# Sheet1.net
KiCad netlist of a schematic drawn in Altium Designer
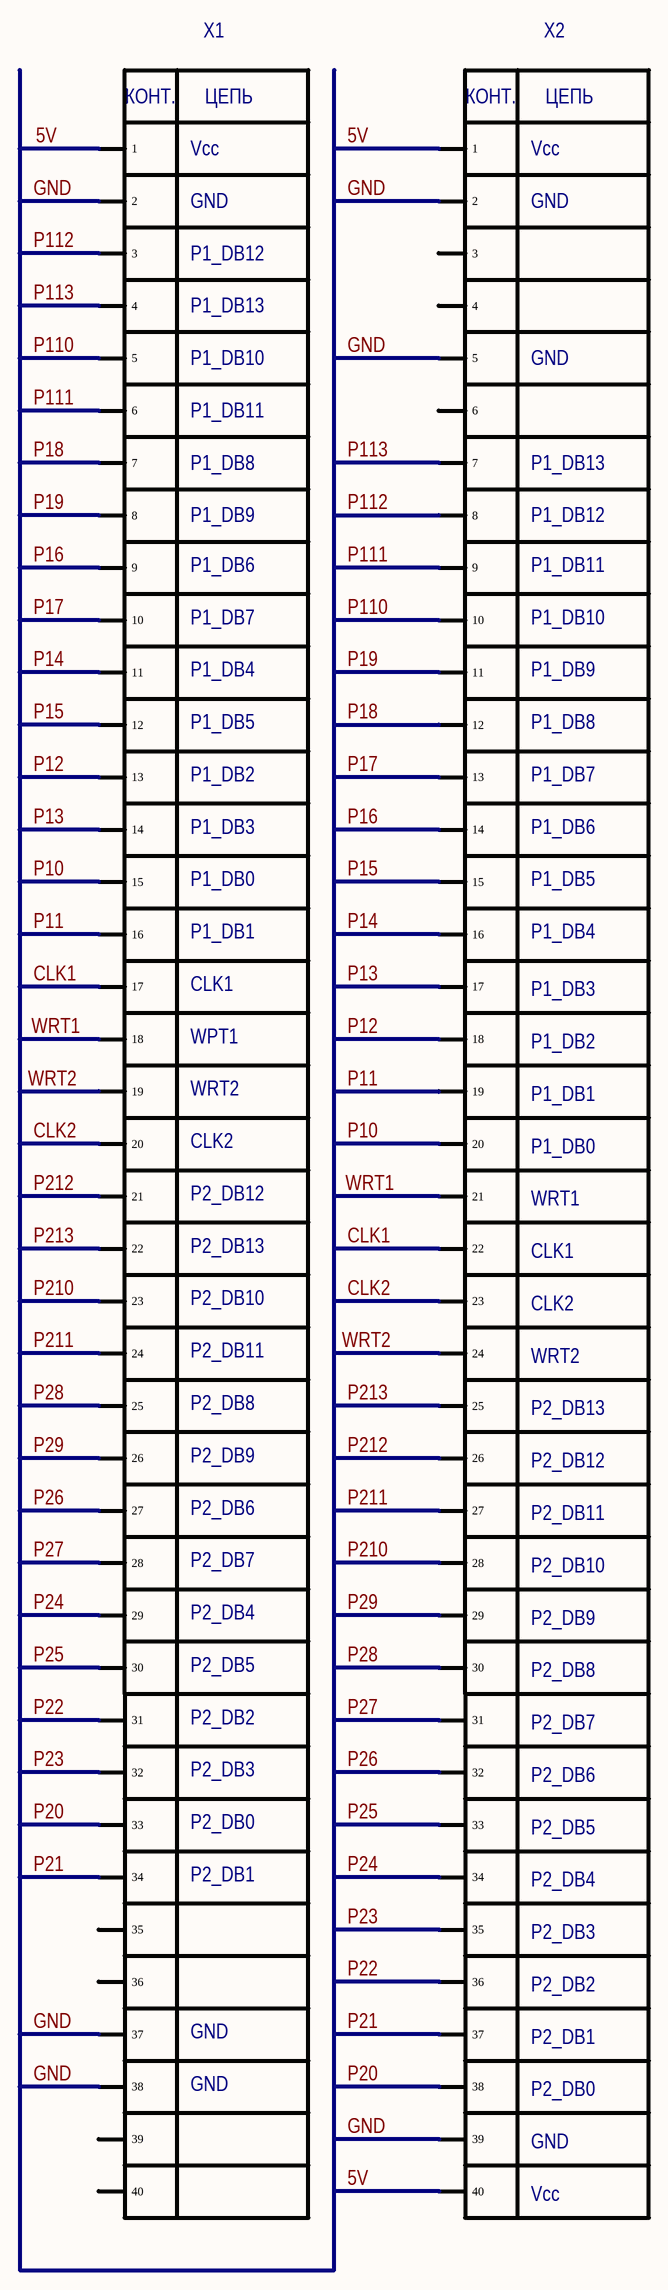
[diagram p0: Sheet1.SchDoc]

(export (version "E")
  (design (tool "Eeschema 10.0.6"))
  (components
    (comp (ref "X1")
      (value "PLD40")
      (footprint "PLD-40")
      (description "Штыри на плату, шаг 2.54мм., двухрядные")
      (libsource (lib "ConnectorsM") (part "PLD40"))
    )
    (comp (ref "X2")
      (value "PLD40")
      (footprint "PLD-40")
      (description "Штыри на плату, шаг 2.54мм., двухрядные")
      (libsource (lib "ConnectorsM") (part "PLD40"))
    )
  )
  (nets
    (net (code "1") (name "/5V") (class "Default")
      (node (ref "X1") (pin "1") (pinfunction "1_1") (pintype "passive"))
      (node (ref "X2") (pin "1") (pinfunction "1_1") (pintype "passive"))
      (node (ref "X2") (pin "40") (pinfunction "40_40") (pintype "passive"))
    )
    (net (code "2") (name "/CLK1") (class "Default")
      (node (ref "X1") (pin "17") (pinfunction "17_17") (pintype "passive"))
      (node (ref "X2") (pin "22") (pinfunction "22_22") (pintype "passive"))
    )
    (net (code "3") (name "/CLK2") (class "Default")
      (node (ref "X1") (pin "20") (pinfunction "20_20") (pintype "passive"))
      (node (ref "X2") (pin "23") (pinfunction "23_23") (pintype "passive"))
    )
    (net (code "4") (name "/GND") (class "Default")
      (node (ref "X1") (pin "2") (pinfunction "2_2") (pintype "passive"))
      (node (ref "X1") (pin "37") (pinfunction "37_37") (pintype "passive"))
      (node (ref "X1") (pin "38") (pinfunction "38_38") (pintype "passive"))
      (node (ref "X2") (pin "2") (pinfunction "2_2") (pintype "passive"))
      (node (ref "X2") (pin "39") (pinfunction "39_39") (pintype "passive"))
      (node (ref "X2") (pin "5") (pinfunction "5_5") (pintype "passive"))
    )
    (net (code "5") (name "/P10") (class "Default")
      (node (ref "X1") (pin "15") (pinfunction "15_15") (pintype "passive"))
      (node (ref "X2") (pin "20") (pinfunction "20_20") (pintype "passive"))
    )
    (net (code "6") (name "/P11") (class "Default")
      (node (ref "X1") (pin "16") (pinfunction "16_16") (pintype "passive"))
      (node (ref "X2") (pin "19") (pinfunction "19_19") (pintype "passive"))
    )
    (net (code "7") (name "/P12") (class "Default")
      (node (ref "X1") (pin "13") (pinfunction "13_13") (pintype "passive"))
      (node (ref "X2") (pin "18") (pinfunction "18_18") (pintype "passive"))
    )
    (net (code "8") (name "/P13") (class "Default")
      (node (ref "X1") (pin "14") (pinfunction "14_14") (pintype "passive"))
      (node (ref "X2") (pin "17") (pinfunction "17_17") (pintype "passive"))
    )
    (net (code "9") (name "/P14") (class "Default")
      (node (ref "X1") (pin "11") (pinfunction "11_11") (pintype "passive"))
      (node (ref "X2") (pin "16") (pinfunction "16_16") (pintype "passive"))
    )
    (net (code "10") (name "/P15") (class "Default")
      (node (ref "X1") (pin "12") (pinfunction "12_12") (pintype "passive"))
      (node (ref "X2") (pin "15") (pinfunction "15_15") (pintype "passive"))
    )
    (net (code "11") (name "/P16") (class "Default")
      (node (ref "X1") (pin "9") (pinfunction "9_9") (pintype "passive"))
      (node (ref "X2") (pin "14") (pinfunction "14_14") (pintype "passive"))
    )
    (net (code "12") (name "/P17") (class "Default")
      (node (ref "X1") (pin "10") (pinfunction "10_10") (pintype "passive"))
      (node (ref "X2") (pin "13") (pinfunction "13_13") (pintype "passive"))
    )
    (net (code "13") (name "/P18") (class "Default")
      (node (ref "X1") (pin "7") (pinfunction "7_7") (pintype "passive"))
      (node (ref "X2") (pin "12") (pinfunction "12_12") (pintype "passive"))
    )
    (net (code "14") (name "/P19") (class "Default")
      (node (ref "X1") (pin "8") (pinfunction "8_8") (pintype "passive"))
      (node (ref "X2") (pin "11") (pinfunction "11_11") (pintype "passive"))
    )
    (net (code "15") (name "/P20") (class "Default")
      (node (ref "X1") (pin "33") (pinfunction "33_33") (pintype "passive"))
      (node (ref "X2") (pin "38") (pinfunction "38_38") (pintype "passive"))
    )
    (net (code "16") (name "/P21") (class "Default")
      (node (ref "X1") (pin "34") (pinfunction "34_34") (pintype "passive"))
      (node (ref "X2") (pin "37") (pinfunction "37_37") (pintype "passive"))
    )
    (net (code "17") (name "/P22") (class "Default")
      (node (ref "X1") (pin "31") (pinfunction "31_31") (pintype "passive"))
      (node (ref "X2") (pin "36") (pinfunction "36_36") (pintype "passive"))
    )
    (net (code "18") (name "/P23") (class "Default")
      (node (ref "X1") (pin "32") (pinfunction "32_32") (pintype "passive"))
      (node (ref "X2") (pin "35") (pinfunction "35_35") (pintype "passive"))
    )
    (net (code "19") (name "/P24") (class "Default")
      (node (ref "X1") (pin "29") (pinfunction "29_29") (pintype "passive"))
      (node (ref "X2") (pin "34") (pinfunction "34_34") (pintype "passive"))
    )
    (net (code "20") (name "/P25") (class "Default")
      (node (ref "X1") (pin "30") (pinfunction "30_30") (pintype "passive"))
      (node (ref "X2") (pin "33") (pinfunction "33_33") (pintype "passive"))
    )
    (net (code "21") (name "/P26") (class "Default")
      (node (ref "X1") (pin "27") (pinfunction "27_27") (pintype "passive"))
      (node (ref "X2") (pin "32") (pinfunction "32_32") (pintype "passive"))
    )
    (net (code "22") (name "/P27") (class "Default")
      (node (ref "X1") (pin "28") (pinfunction "28_28") (pintype "passive"))
      (node (ref "X2") (pin "31") (pinfunction "31_31") (pintype "passive"))
    )
    (net (code "23") (name "/P28") (class "Default")
      (node (ref "X1") (pin "25") (pinfunction "25_25") (pintype "passive"))
      (node (ref "X2") (pin "30") (pinfunction "30_30") (pintype "passive"))
    )
    (net (code "24") (name "/P29") (class "Default")
      (node (ref "X1") (pin "26") (pinfunction "26_26") (pintype "passive"))
      (node (ref "X2") (pin "29") (pinfunction "29_29") (pintype "passive"))
    )
    (net (code "25") (name "/P110") (class "Default")
      (node (ref "X1") (pin "5") (pinfunction "5_5") (pintype "passive"))
      (node (ref "X2") (pin "10") (pinfunction "10_10") (pintype "passive"))
    )
    (net (code "26") (name "/P111") (class "Default")
      (node (ref "X1") (pin "6") (pinfunction "6_6") (pintype "passive"))
      (node (ref "X2") (pin "9") (pinfunction "9_9") (pintype "passive"))
    )
    (net (code "27") (name "/P112") (class "Default")
      (node (ref "X1") (pin "3") (pinfunction "3_3") (pintype "passive"))
      (node (ref "X2") (pin "8") (pinfunction "8_8") (pintype "passive"))
    )
    (net (code "28") (name "/P113") (class "Default")
      (node (ref "X1") (pin "4") (pinfunction "4_4") (pintype "passive"))
      (node (ref "X2") (pin "7") (pinfunction "7_7") (pintype "passive"))
    )
    (net (code "29") (name "/P210") (class "Default")
      (node (ref "X1") (pin "23") (pinfunction "23_23") (pintype "passive"))
      (node (ref "X2") (pin "28") (pinfunction "28_28") (pintype "passive"))
    )
    (net (code "30") (name "/P211") (class "Default")
      (node (ref "X1") (pin "24") (pinfunction "24_24") (pintype "passive"))
      (node (ref "X2") (pin "27") (pinfunction "27_27") (pintype "passive"))
    )
    (net (code "31") (name "/P212") (class "Default")
      (node (ref "X1") (pin "21") (pinfunction "21_21") (pintype "passive"))
      (node (ref "X2") (pin "26") (pinfunction "26_26") (pintype "passive"))
    )
    (net (code "32") (name "/P213") (class "Default")
      (node (ref "X1") (pin "22") (pinfunction "22_22") (pintype "passive"))
      (node (ref "X2") (pin "25") (pinfunction "25_25") (pintype "passive"))
    )
    (net (code "33") (name "/WRT1") (class "Default")
      (node (ref "X1") (pin "18") (pinfunction "18_18") (pintype "passive"))
      (node (ref "X2") (pin "21") (pinfunction "21_21") (pintype "passive"))
    )
    (net (code "34") (name "/WRT2") (class "Default")
      (node (ref "X1") (pin "19") (pinfunction "19_19") (pintype "passive"))
      (node (ref "X2") (pin "24") (pinfunction "24_24") (pintype "passive"))
    )
    (net (code "35") (name "unconnected-(X1-Pad35)") (class "Default")
      (node (ref "X1") (pin "35") (pinfunction "35_35") (pintype "passive"))
    )
    (net (code "36") (name "unconnected-(X1-Pad36)") (class "Default")
      (node (ref "X1") (pin "36") (pinfunction "36_36") (pintype "passive"))
    )
    (net (code "37") (name "unconnected-(X1-Pad39)") (class "Default")
      (node (ref "X1") (pin "39") (pinfunction "39_39") (pintype "passive"))
    )
    (net (code "38") (name "unconnected-(X1-Pad40)") (class "Default")
      (node (ref "X1") (pin "40") (pinfunction "40_40") (pintype "passive"))
    )
    (net (code "39") (name "unconnected-(X2-Pad3)") (class "Default")
      (node (ref "X2") (pin "3") (pinfunction "3_3") (pintype "passive"))
    )
    (net (code "40") (name "unconnected-(X2-Pad4)") (class "Default")
      (node (ref "X2") (pin "4") (pinfunction "4_4") (pintype "passive"))
    )
    (net (code "41") (name "unconnected-(X2-Pad6)") (class "Default")
      (node (ref "X2") (pin "6") (pinfunction "6_6") (pintype "passive"))
    )
  )
)
